# P06_Boot.net
KiCad netlist of a schematic drawn in Altium Designer
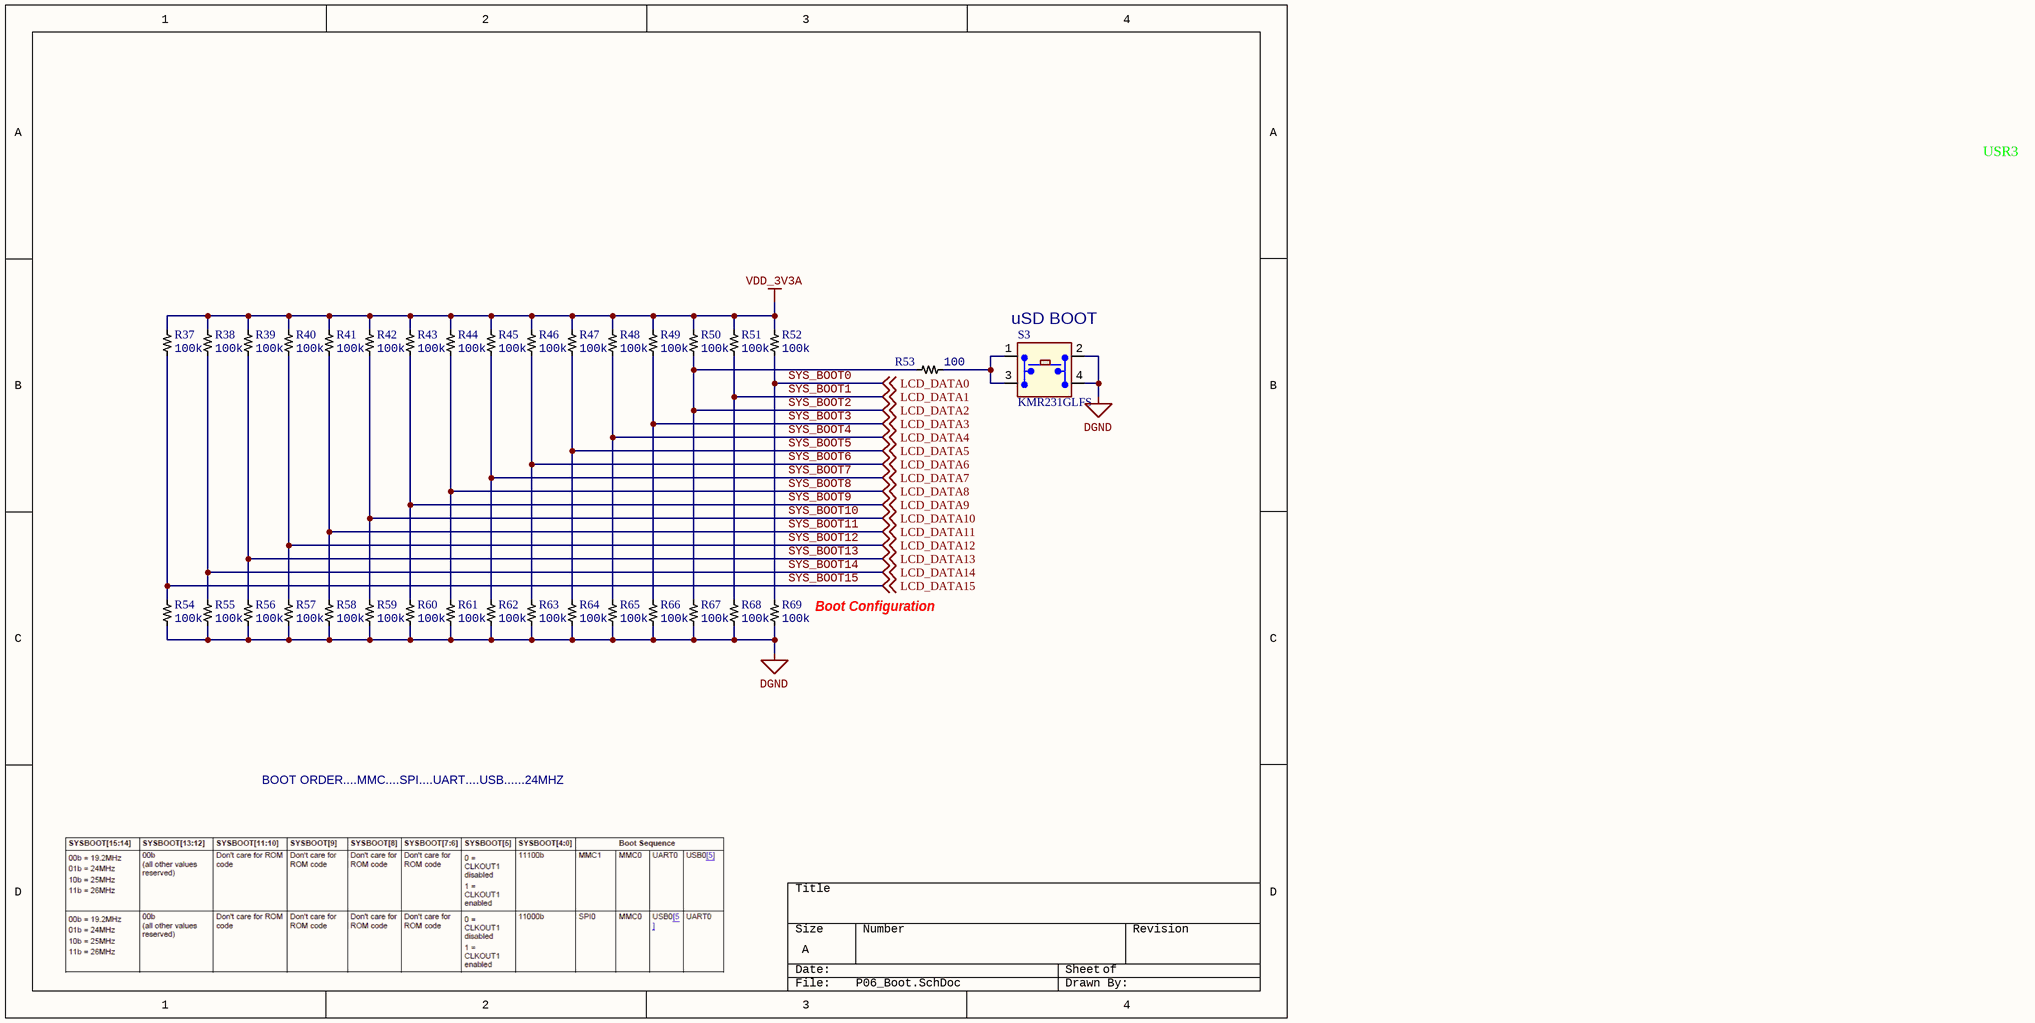
[diagram p0: P06_Boot.SchDoc]

(export (version "E")
  (design (tool "Eeschema 10.0.6"))
  (components
    (comp (ref "R37")
      (value "RC0402FR-07100KL")
      (footprint "Orient:RES0402")
      (description "Resistor 100kOhm 0402 SMD")
      (fields
        (field (name "MANUFACTURER") "Yageo")
        (field (name "TOLERANCE") "1%")
        (field (name "RESISTANCE") "100k")
      )
      (libsource (lib "Orient") (part "RES_100k"))
    )
    (comp (ref "R38")
      (value "RC0402FR-07100KL")
      (footprint "Orient:RES0402")
      (description "Resistor 100kOhm 0402 SMD")
      (fields
        (field (name "MANUFACTURER") "Yageo")
        (field (name "TOLERANCE") "1%")
        (field (name "RESISTANCE") "100k")
      )
      (libsource (lib "Orient") (part "RES_100k"))
    )
    (comp (ref "R39")
      (value "RC0402FR-07100KL")
      (footprint "Orient:RES0402")
      (description "Resistor 100kOhm 0402 SMD")
      (fields
        (field (name "MANUFACTURER") "Yageo")
        (field (name "TOLERANCE") "1%")
        (field (name "RESISTANCE") "100k")
      )
      (libsource (lib "Orient") (part "RES_100k"))
    )
    (comp (ref "R40")
      (value "RC0402FR-07100KL")
      (footprint "Orient:RES0402")
      (description "Resistor 100kOhm 0402 SMD")
      (fields
        (field (name "MANUFACTURER") "Yageo")
        (field (name "TOLERANCE") "1%")
        (field (name "RESISTANCE") "100k")
      )
      (libsource (lib "Orient") (part "RES_100k"))
    )
    (comp (ref "R41")
      (value "RC0402FR-07100KL")
      (footprint "Orient:RES0402")
      (description "Resistor 100kOhm 0402 SMD")
      (fields
        (field (name "MANUFACTURER") "Yageo")
        (field (name "TOLERANCE") "1%")
        (field (name "RESISTANCE") "100k")
      )
      (libsource (lib "Orient") (part "RES_100k"))
    )
    (comp (ref "R42")
      (value "RC0402FR-07100KL")
      (footprint "Orient:RES0402")
      (description "Resistor 100kOhm 0402 SMD")
      (fields
        (field (name "MANUFACTURER") "Yageo")
        (field (name "TOLERANCE") "1%")
        (field (name "RESISTANCE") "100k")
      )
      (libsource (lib "Orient") (part "RES_100k"))
    )
    (comp (ref "R43")
      (value "RC0402FR-07100KL")
      (footprint "Orient:RES0402")
      (description "Resistor 100kOhm 0402 SMD")
      (fields
        (field (name "MANUFACTURER") "Yageo")
        (field (name "TOLERANCE") "1%")
        (field (name "RESISTANCE") "100k")
      )
      (libsource (lib "Orient") (part "RES_100k"))
    )
    (comp (ref "R44")
      (value "RC0402FR-07100KL")
      (footprint "Orient:RES0402")
      (description "Resistor 100kOhm 0402 SMD")
      (fields
        (field (name "MANUFACTURER") "Yageo")
        (field (name "TOLERANCE") "1%")
        (field (name "RESISTANCE") "100k")
      )
      (libsource (lib "Orient") (part "RES_100k"))
    )
    (comp (ref "R45")
      (value "RC0402FR-07100KL")
      (footprint "Orient:RES0402")
      (description "Resistor 100kOhm 0402 SMD")
      (fields
        (field (name "MANUFACTURER") "Yageo")
        (field (name "TOLERANCE") "1%")
        (field (name "RESISTANCE") "100k")
      )
      (libsource (lib "Orient") (part "RES_100k"))
    )
    (comp (ref "R46")
      (value "RC0402FR-07100KL")
      (footprint "Orient:RES0402")
      (description "Resistor 100kOhm 0402 SMD")
      (fields
        (field (name "MANUFACTURER") "Yageo")
        (field (name "TOLERANCE") "1%")
        (field (name "RESISTANCE") "100k")
      )
      (libsource (lib "Orient") (part "RES_100k"))
    )
    (comp (ref "R47")
      (value "RC0402FR-07100KL")
      (footprint "Orient:RES0402")
      (description "Resistor 100kOhm 0402 SMD")
      (fields
        (field (name "MANUFACTURER") "Yageo")
        (field (name "TOLERANCE") "1%")
        (field (name "RESISTANCE") "100k")
      )
      (libsource (lib "Orient") (part "RES_100k"))
    )
    (comp (ref "R48")
      (value "RC0402FR-07100KL")
      (footprint "Orient:RES0402")
      (description "Resistor 100kOhm 0402 SMD")
      (fields
        (field (name "MANUFACTURER") "Yageo")
        (field (name "TOLERANCE") "1%")
        (field (name "RESISTANCE") "100k")
      )
      (libsource (lib "Orient") (part "RES_100k"))
    )
    (comp (ref "R49")
      (value "RC0402FR-07100KL")
      (footprint "Orient:RES0402")
      (description "Resistor 100kOhm 0402 SMD")
      (fields
        (field (name "MANUFACTURER") "Yageo")
        (field (name "TOLERANCE") "1%")
        (field (name "RESISTANCE") "100k")
      )
      (libsource (lib "Orient") (part "RES_100k"))
    )
    (comp (ref "R50")
      (value "RC0402FR-07100KL")
      (footprint "Orient:RES0402")
      (description "Resistor 100kOhm 0402 SMD")
      (fields
        (field (name "MANUFACTURER") "Yageo")
        (field (name "TOLERANCE") "1%")
        (field (name "RESISTANCE") "100k")
      )
      (libsource (lib "Orient") (part "RES_100k"))
    )
    (comp (ref "R51")
      (value "RC0402FR-07100KL")
      (footprint "Orient:RES0402")
      (description "Resistor 100kOhm 0402 SMD")
      (fields
        (field (name "MANUFACTURER") "Yageo")
        (field (name "TOLERANCE") "1%")
        (field (name "RESISTANCE") "100k")
      )
      (libsource (lib "Orient") (part "RES_100k"))
    )
    (comp (ref "R52")
      (value "RC0402FR-07100KL")
      (footprint "Orient:RES0402")
      (description "Resistor 100kOhm 0402 SMD")
      (fields
        (field (name "MANUFACTURER") "Yageo")
        (field (name "TOLERANCE") "1%")
        (field (name "RESISTANCE") "100k")
      )
      (libsource (lib "Orient") (part "RES_100k"))
    )
    (comp (ref "R53")
      (value "RC0402FR-07100RL")
      (footprint "Orient:RES0402")
      (description "Resistor 100Ohm 0402 SMD")
      (fields
        (field (name "MANUFACTURER") "Yageo")
        (field (name "TOLERANCE") "1%")
        (field (name "RESISTANCE") "100")
      )
      (libsource (lib "Orient") (part "RES_100"))
    )
    (comp (ref "R54")
      (value "RC0402FR-07100KL")
      (footprint "Orient:RES0402")
      (description "Resistor 100kOhm 0402 SMD")
      (fields
        (field (name "MANUFACTURER") "Yageo")
        (field (name "TOLERANCE") "1%")
        (field (name "RESISTANCE") "100k")
      )
      (libsource (lib "Orient") (part "RES_100k"))
    )
    (comp (ref "R55")
      (value "RC0402FR-07100KL")
      (footprint "Orient:RES0402")
      (description "Resistor 100kOhm 0402 SMD")
      (fields
        (field (name "MANUFACTURER") "Yageo")
        (field (name "TOLERANCE") "1%")
        (field (name "RESISTANCE") "100k")
      )
      (libsource (lib "Orient") (part "RES_100k"))
    )
    (comp (ref "R56")
      (value "RC0402FR-07100KL")
      (footprint "Orient:RES0402")
      (description "Resistor 100kOhm 0402 SMD")
      (fields
        (field (name "MANUFACTURER") "Yageo")
        (field (name "TOLERANCE") "1%")
        (field (name "RESISTANCE") "100k")
      )
      (libsource (lib "Orient") (part "RES_100k"))
    )
    (comp (ref "R57")
      (value "RC0402FR-07100KL")
      (footprint "Orient:RES0402")
      (description "Resistor 100kOhm 0402 SMD")
      (fields
        (field (name "MANUFACTURER") "Yageo")
        (field (name "TOLERANCE") "1%")
        (field (name "RESISTANCE") "100k")
      )
      (libsource (lib "Orient") (part "RES_100k"))
    )
    (comp (ref "R58")
      (value "RC0402FR-07100KL")
      (footprint "Orient:RES0402")
      (description "Resistor 100kOhm 0402 SMD")
      (fields
        (field (name "MANUFACTURER") "Yageo")
        (field (name "TOLERANCE") "1%")
        (field (name "RESISTANCE") "100k")
      )
      (libsource (lib "Orient") (part "RES_100k"))
    )
    (comp (ref "R59")
      (value "RC0402FR-07100KL")
      (footprint "Orient:RES0402")
      (description "Resistor 100kOhm 0402 SMD")
      (fields
        (field (name "MANUFACTURER") "Yageo")
        (field (name "TOLERANCE") "1%")
        (field (name "RESISTANCE") "100k")
      )
      (libsource (lib "Orient") (part "RES_100k"))
    )
    (comp (ref "R60")
      (value "RC0402FR-07100KL")
      (footprint "Orient:RES0402")
      (description "Resistor 100kOhm 0402 SMD")
      (fields
        (field (name "MANUFACTURER") "Yageo")
        (field (name "TOLERANCE") "1%")
        (field (name "RESISTANCE") "100k")
      )
      (libsource (lib "Orient") (part "RES_100k"))
    )
    (comp (ref "R61")
      (value "RC0402FR-07100KL")
      (footprint "Orient:RES0402")
      (description "Resistor 100kOhm 0402 SMD")
      (fields
        (field (name "MANUFACTURER") "Yageo")
        (field (name "TOLERANCE") "1%")
        (field (name "RESISTANCE") "100k")
      )
      (libsource (lib "Orient") (part "RES_100k"))
    )
    (comp (ref "R62")
      (value "RC0402FR-07100KL")
      (footprint "Orient:RES0402")
      (description "Resistor 100kOhm 0402 SMD")
      (fields
        (field (name "MANUFACTURER") "Yageo")
        (field (name "TOLERANCE") "1%")
        (field (name "RESISTANCE") "100k")
      )
      (libsource (lib "Orient") (part "RES_100k"))
    )
    (comp (ref "R63")
      (value "RC0402FR-07100KL")
      (footprint "Orient:RES0402")
      (description "Resistor 100kOhm 0402 SMD")
      (fields
        (field (name "MANUFACTURER") "Yageo")
        (field (name "TOLERANCE") "1%")
        (field (name "RESISTANCE") "100k")
      )
      (libsource (lib "Orient") (part "RES_100k"))
    )
    (comp (ref "R64")
      (value "RC0402FR-07100KL")
      (footprint "Orient:RES0402")
      (description "Resistor 100kOhm 0402 SMD")
      (fields
        (field (name "MANUFACTURER") "Yageo")
        (field (name "TOLERANCE") "1%")
        (field (name "RESISTANCE") "100k")
      )
      (libsource (lib "Orient") (part "RES_100k"))
    )
    (comp (ref "R65")
      (value "RC0402FR-07100KL")
      (footprint "Orient:RES0402")
      (description "Resistor 100kOhm 0402 SMD")
      (fields
        (field (name "MANUFACTURER") "Yageo")
        (field (name "TOLERANCE") "1%")
        (field (name "RESISTANCE") "100k")
      )
      (libsource (lib "Orient") (part "RES_100k"))
    )
    (comp (ref "R66")
      (value "RC0402FR-07100KL")
      (footprint "Orient:RES0402")
      (description "Resistor 100kOhm 0402 SMD")
      (fields
        (field (name "MANUFACTURER") "Yageo")
        (field (name "TOLERANCE") "1%")
        (field (name "RESISTANCE") "100k")
      )
      (libsource (lib "Orient") (part "RES_100k"))
    )
    (comp (ref "R67")
      (value "RC0402FR-07100KL")
      (footprint "Orient:RES0402")
      (description "Resistor 100kOhm 0402 SMD")
      (fields
        (field (name "MANUFACTURER") "Yageo")
        (field (name "TOLERANCE") "1%")
        (field (name "RESISTANCE") "100k")
      )
      (libsource (lib "Orient") (part "RES_100k"))
    )
    (comp (ref "R68")
      (value "RC0402FR-07100KL")
      (footprint "Orient:RES0402")
      (description "Resistor 100kOhm 0402 SMD")
      (fields
        (field (name "MANUFACTURER") "Yageo")
        (field (name "TOLERANCE") "1%")
        (field (name "RESISTANCE") "100k")
      )
      (libsource (lib "Orient") (part "RES_100k"))
    )
    (comp (ref "R69")
      (value "RC0402FR-07100KL")
      (footprint "Orient:RES0402")
      (description "Resistor 100kOhm 0402 SMD")
      (fields
        (field (name "MANUFACTURER") "Yageo")
        (field (name "TOLERANCE") "1%")
        (field (name "RESISTANCE") "100k")
      )
      (libsource (lib "Orient") (part "RES_100k"))
    )
    (comp (ref "S3")
      (value "KMR231GLFS")
      (footprint "Orient:SW4SMD_63X161LS")
      (description "Microminiature Tact Switch for SMT")
      (fields (field (name "MANUFACTURER") "C&K Components"))
      (libsource (lib "Orient") (part "KMR2"))
    )
  )
  (nets
    (net (code "1") (name "DGND") (class "Default")
      (node (ref "R54") (pin "1") (pintype "passive"))
      (node (ref "R55") (pin "1") (pintype "passive"))
      (node (ref "R56") (pin "1") (pintype "passive"))
      (node (ref "R57") (pin "1") (pintype "passive"))
      (node (ref "R58") (pin "1") (pintype "passive"))
      (node (ref "R59") (pin "1") (pintype "passive"))
      (node (ref "R60") (pin "1") (pintype "passive"))
      (node (ref "R61") (pin "1") (pintype "passive"))
      (node (ref "R62") (pin "1") (pintype "passive"))
      (node (ref "R63") (pin "1") (pintype "passive"))
      (node (ref "R64") (pin "1") (pintype "passive"))
      (node (ref "R65") (pin "1") (pintype "passive"))
      (node (ref "R66") (pin "1") (pintype "passive"))
      (node (ref "R67") (pin "1") (pintype "passive"))
      (node (ref "R68") (pin "1") (pintype "passive"))
      (node (ref "R69") (pin "1") (pintype "passive"))
      (node (ref "S3") (pin "2") (pinfunction "A2_2") (pintype "passive"))
      (node (ref "S3") (pin "4") (pinfunction "4_4") (pintype "power_in"))
    )
    (net (code "2") (name "LCD_DATA0") (class "Default")
      (node (ref "R52") (pin "1") (pintype "passive"))
      (node (ref "R69") (pin "2") (pintype "passive"))
    )
    (net (code "3") (name "LCD_DATA1") (class "Default")
      (node (ref "R51") (pin "1") (pintype "passive"))
      (node (ref "R68") (pin "2") (pintype "passive"))
    )
    (net (code "4") (name "LCD_DATA2") (class "Default")
      (node (ref "R50") (pin "1") (pintype "passive"))
      (node (ref "R53") (pin "1") (pintype "passive"))
      (node (ref "R67") (pin "2") (pintype "passive"))
    )
    (net (code "5") (name "LCD_DATA3") (class "Default")
      (node (ref "R49") (pin "1") (pintype "passive"))
      (node (ref "R66") (pin "2") (pintype "passive"))
    )
    (net (code "6") (name "LCD_DATA4") (class "Default")
      (node (ref "R48") (pin "1") (pintype "passive"))
      (node (ref "R65") (pin "2") (pintype "passive"))
    )
    (net (code "7") (name "LCD_DATA5") (class "Default")
      (node (ref "R47") (pin "1") (pintype "passive"))
      (node (ref "R64") (pin "2") (pintype "passive"))
    )
    (net (code "8") (name "LCD_DATA6") (class "Default")
      (node (ref "R46") (pin "1") (pintype "passive"))
      (node (ref "R63") (pin "2") (pintype "passive"))
    )
    (net (code "9") (name "LCD_DATA7") (class "Default")
      (node (ref "R45") (pin "1") (pintype "passive"))
      (node (ref "R62") (pin "2") (pintype "passive"))
    )
    (net (code "10") (name "LCD_DATA8") (class "Default")
      (node (ref "R44") (pin "1") (pintype "passive"))
      (node (ref "R61") (pin "2") (pintype "passive"))
    )
    (net (code "11") (name "LCD_DATA9") (class "Default")
      (node (ref "R43") (pin "1") (pintype "passive"))
      (node (ref "R60") (pin "2") (pintype "passive"))
    )
    (net (code "12") (name "LCD_DATA10") (class "Default")
      (node (ref "R42") (pin "1") (pintype "passive"))
      (node (ref "R59") (pin "2") (pintype "passive"))
    )
    (net (code "13") (name "LCD_DATA11") (class "Default")
      (node (ref "R41") (pin "1") (pintype "passive"))
      (node (ref "R58") (pin "2") (pintype "passive"))
    )
    (net (code "14") (name "LCD_DATA12") (class "Default")
      (node (ref "R40") (pin "1") (pintype "passive"))
      (node (ref "R57") (pin "2") (pintype "passive"))
    )
    (net (code "15") (name "LCD_DATA13") (class "Default")
      (node (ref "R39") (pin "1") (pintype "passive"))
      (node (ref "R56") (pin "2") (pintype "passive"))
    )
    (net (code "16") (name "LCD_DATA14") (class "Default")
      (node (ref "R38") (pin "1") (pintype "passive"))
      (node (ref "R55") (pin "2") (pintype "passive"))
    )
    (net (code "17") (name "LCD_DATA15") (class "Default")
      (node (ref "R37") (pin "1") (pintype "passive"))
      (node (ref "R54") (pin "2") (pintype "passive"))
    )
    (net (code "18") (name "Net-(S3-A1)") (class "Default")
      (node (ref "R53") (pin "2") (pintype "passive"))
      (node (ref "S3") (pin "1") (pinfunction "A1_1") (pintype "passive"))
      (node (ref "S3") (pin "3") (pinfunction "A3_3") (pintype "passive"))
    )
    (net (code "19") (name "VDD_3V3A") (class "Default")
      (node (ref "R37") (pin "2") (pintype "passive"))
      (node (ref "R38") (pin "2") (pintype "passive"))
      (node (ref "R39") (pin "2") (pintype "passive"))
      (node (ref "R40") (pin "2") (pintype "passive"))
      (node (ref "R41") (pin "2") (pintype "passive"))
      (node (ref "R42") (pin "2") (pintype "passive"))
      (node (ref "R43") (pin "2") (pintype "passive"))
      (node (ref "R44") (pin "2") (pintype "passive"))
      (node (ref "R45") (pin "2") (pintype "passive"))
      (node (ref "R46") (pin "2") (pintype "passive"))
      (node (ref "R47") (pin "2") (pintype "passive"))
      (node (ref "R48") (pin "2") (pintype "passive"))
      (node (ref "R49") (pin "2") (pintype "passive"))
      (node (ref "R50") (pin "2") (pintype "passive"))
      (node (ref "R51") (pin "2") (pintype "passive"))
      (node (ref "R52") (pin "2") (pintype "passive"))
    )
  )
)
